# 3_viper_eagle_rep-mcu.net
KiCad netlist of a schematic drawn in Altium Designer
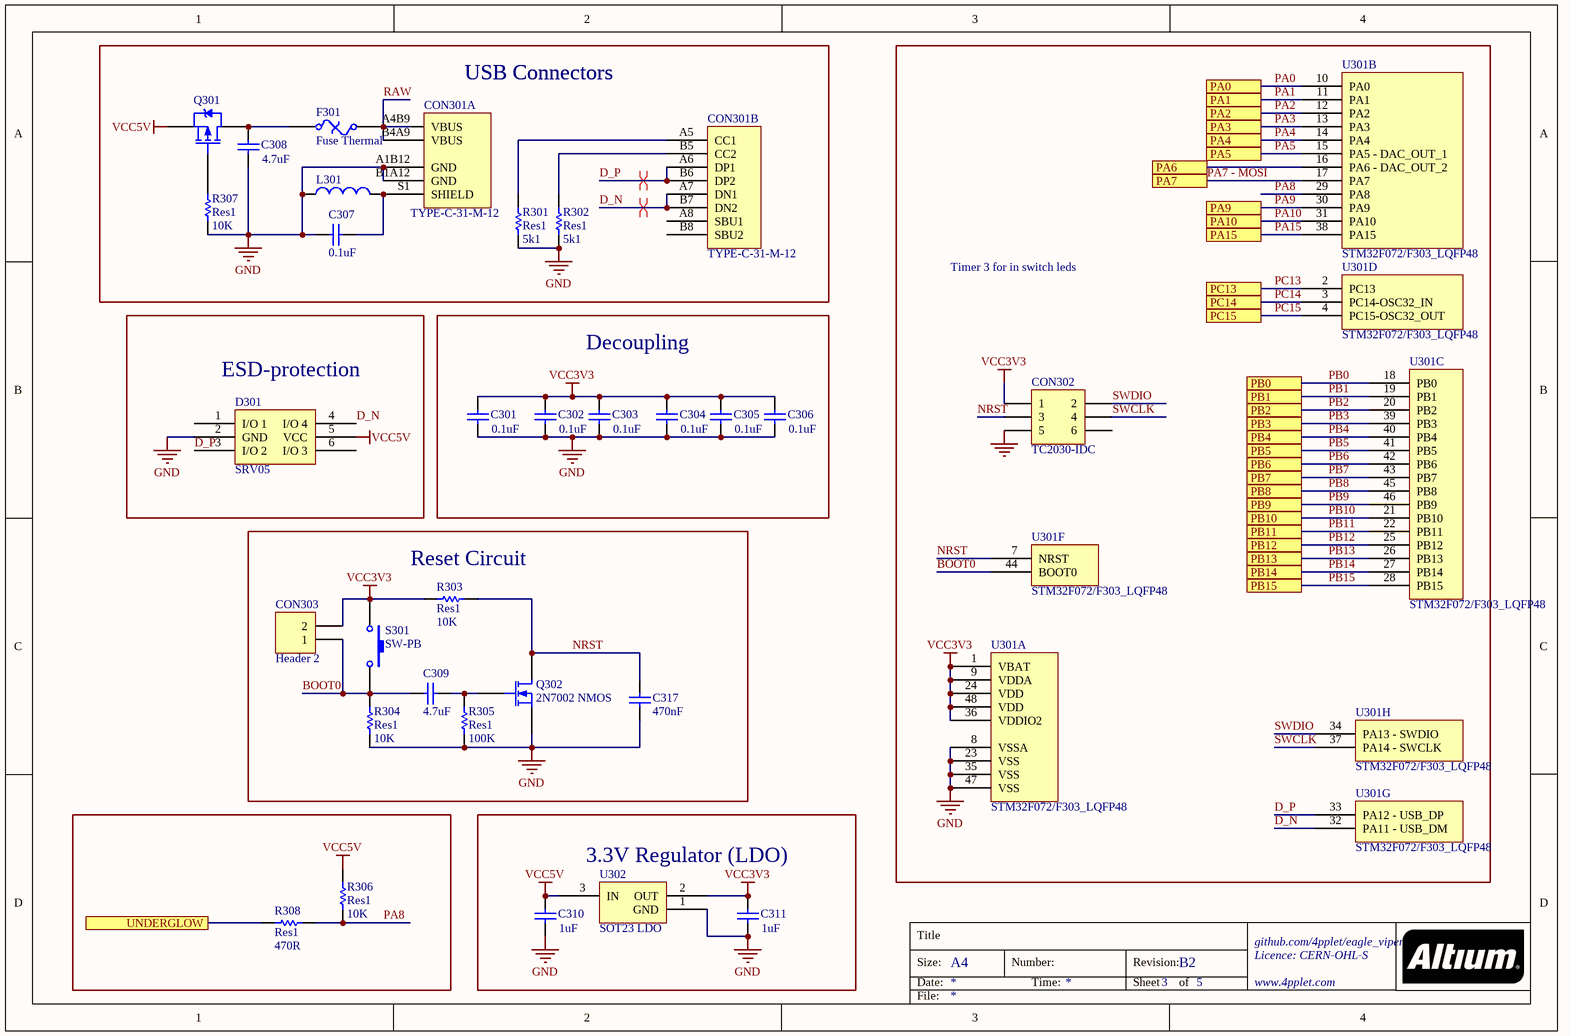
[diagram p0: 3_viper_eagle_rep-mcu.SchDoc]

(export (version "E")
  (design (tool "Eeschema 10.0.6"))
  (components
    (comp (ref "C301")
      (value "0.1uF")
      (footprint "C0603[1608]")
      (description "Capacitor")
      (fields (field (name "LCSC PART #") "C14663") (field (name "MRF.PART") "CC0603KRX7R9BB104"))
      (libsource (lib "Miscellaneous Devices") (part "Cap"))
    )
    (comp (ref "C302")
      (value "0.1uF")
      (footprint "C0603[1608]")
      (description "Capacitor")
      (fields (field (name "LCSC PART #") "C14663") (field (name "MRF.PART") "CC0603KRX7R9BB104"))
      (libsource (lib "Miscellaneous Devices") (part "Cap"))
    )
    (comp (ref "C303")
      (value "0.1uF")
      (footprint "C0603[1608]")
      (description "Capacitor")
      (fields (field (name "LCSC PART #") "C14663") (field (name "MRF.PART") "CC0603KRX7R9BB104"))
      (libsource (lib "Miscellaneous Devices") (part "Cap"))
    )
    (comp (ref "C304")
      (value "0.1uF")
      (footprint "C0603[1608]")
      (description "Capacitor")
      (fields (field (name "LCSC PART #") "C14663") (field (name "MRF.PART") "CC0603KRX7R9BB104"))
      (libsource (lib "Miscellaneous Devices") (part "Cap"))
    )
    (comp (ref "C305")
      (value "0.1uF")
      (footprint "C0603[1608]")
      (description "Capacitor")
      (fields (field (name "LCSC PART #") "C14663") (field (name "MRF.PART") "CC0603KRX7R9BB104"))
      (libsource (lib "Miscellaneous Devices") (part "Cap"))
    )
    (comp (ref "C306")
      (value "0.1uF")
      (footprint "C0603[1608]")
      (description "Capacitor")
      (fields (field (name "LCSC PART #") "C14663") (field (name "MRF.PART") "CC0603KRX7R9BB104"))
      (libsource (lib "Miscellaneous Devices") (part "Cap"))
    )
    (comp (ref "C307")
      (value "0.1uF")
      (footprint "C0603[1608]")
      (description "Capacitor")
      (fields (field (name "LCSC PART #") "C14663") (field (name "MRF.PART") "CC0603KRX7R9BB104"))
      (libsource (lib "Miscellaneous Devices") (part "Cap"))
    )
    (comp (ref "C308")
      (value "4.7uF")
      (footprint "C0603[1608]")
      (description "Capacitor")
      (fields (field (name "LCSC PART #") "C19666") (field (name "MRF.PART") "CL10A475KO8NNNC"))
      (libsource (lib "Miscellaneous Devices") (part "Cap"))
    )
    (comp (ref "C309")
      (value "4.7uF")
      (footprint "C0603[1608]")
      (description "Capacitor")
      (fields (field (name "LCSC PART #") "C19666") (field (name "MRF.PART") "CL10A475KO8NNNC"))
      (libsource (lib "Miscellaneous Devices") (part "Cap"))
    )
    (comp (ref "C310")
      (value "1uF")
      (footprint "C0603[1608]")
      (description "Capacitor")
      (fields (field (name "LCSC PART #") "C15849") (field (name "MRF.PART") "CL10A105KB8NNNC"))
      (libsource (lib "Miscellaneous Devices") (part "Cap"))
    )
    (comp (ref "C311")
      (value "1uF")
      (footprint "C0603[1608]")
      (description "Capacitor")
      (fields (field (name "LCSC PART #") "C15849") (field (name "MRF.PART") "CL10A105KB8NNNC"))
      (libsource (lib "Miscellaneous Devices") (part "Cap"))
    )
    (comp (ref "C317")
      (value "470nF")
      (footprint "C0603[1608]")
      (description "Capacitor")
      (fields (field (name "LCSC PART #") "C1623") (field (name "MRF.PART") "CL10B474KA8NNNC"))
      (libsource (lib "Miscellaneous Devices") (part "Cap"))
    )
    (comp (ref "CON301")
      (value "TYPE-C-31-M-12")
      (footprint "TYPE-C-31-M-12")
      (fields (field (name "LCSC PART #") "C165948"))
      (libsource (lib "Schlib1") (part "TYPE-C-31-M-12"))
    )
    (comp (ref "CON302")
      (value "TC2030-IDC")
      (footprint "TC2030-IDC-NL")
      (description "Header, 3-Pin, Dual row")
      (libsource (lib "Miscellaneous Connectors") (part "Header 3X2"))
    )
    (comp (ref "CON303")
      (value "Header 2")
      (footprint "HDR1X2")
      (description "Header, 2-Pin")
      (libsource (lib "Miscellaneous Connectors") (part "Header 2"))
    )
    (comp (ref "D301")
      (value "SRV05")
      (footprint "SOT-23-6")
      (fields (field (name "LCSC PART #") "C85364") (field (name "MRF.PART") "SRV05-4-P-T7"))
      (libsource (lib "Keebs") (part "SRV05"))
    )
    (comp (ref "F301")
      (value "Fuse Thermal")
      (footprint "C1206[3216]")
      (description "Thermal Fuse")
      (fields (field (name "LCSC PART #") "C135338") (field (name "MRF.PART") "ASMD1206-050"))
      (libsource (lib "Miscellaneous Devices") (part "Fuse Thermal"))
    )
    (comp (ref "L301")
      (value "Inductor")
      (footprint "L0805")
      (fields (field (name "LCSC PART #") "C1015") (field (name "MRF.PART") "GZ2012D101TF"))
      (libsource (lib "Simulation Generic Components") (part "Inductor"))
    )
    (comp (ref "Q301")
      (value "PMOS-2")
      (footprint "SOT-23-3")
      (description "P-Channel Power MOSFET")
      (fields (field (name "LCSC PART #") "C10487") (field (name "MRF.PART") "SI2301CDS-T1-GE3"))
      (libsource (lib "Miscellaneous Devices") (part "PMOS-2"))
    )
    (comp (ref "Q302")
      (value "2N7002 NMOS")
      (footprint "SOT-23-3")
      (description "N-Channel MOSFET")
      (fields (field (name "LCSC PART #") "C8545") (field (name "MRF.PART") "2N7002"))
      (libsource (lib "Miscellaneous Devices") (part "MOSFET-N"))
    )
    (comp (ref "R301")
      (value "Res1")
      (footprint "R0603[1608]")
      (description "Resistor")
      (fields
        (field (name "ALTIUM_VALUE") "5k1")
        (field (name "LCSC PART #") "C23186")
        (field (name "MRF.PART") "0603WAF5101T5E")
      )
      (libsource (lib "Miscellaneous Devices") (part "Res1"))
    )
    (comp (ref "R302")
      (value "Res1")
      (footprint "R0603[1608]")
      (description "Resistor")
      (fields
        (field (name "ALTIUM_VALUE") "5k1")
        (field (name "LCSC PART #") "C23186")
        (field (name "MRF.PART") "0603WAF5101T5E")
      )
      (libsource (lib "Miscellaneous Devices") (part "Res1"))
    )
    (comp (ref "R303")
      (value "Res1")
      (footprint "R0603[1608]")
      (description "Resistor")
      (fields
        (field (name "ALTIUM_VALUE") "10K")
        (field (name "LCSC PART #") "C25804")
        (field (name "MRF.PART") "0603WAF1002T5E")
      )
      (libsource (lib "Miscellaneous Devices") (part "Res1"))
    )
    (comp (ref "R304")
      (value "Res1")
      (footprint "R0603[1608]")
      (description "Resistor")
      (fields
        (field (name "ALTIUM_VALUE") "10K")
        (field (name "LCSC PART #") "C25804")
        (field (name "MRF.PART") "0603WAF1002T5E")
      )
      (libsource (lib "Miscellaneous Devices") (part "Res1"))
    )
    (comp (ref "R305")
      (value "Res1")
      (footprint "R0603[1608]")
      (description "Resistor")
      (fields
        (field (name "ALTIUM_VALUE") "100K")
        (field (name "LCSC PART #") "C25803")
        (field (name "MRF.PART") "0603WAF1003T5E")
      )
      (libsource (lib "Miscellaneous Devices") (part "Res1"))
    )
    (comp (ref "R306")
      (value "Res1")
      (footprint "R0603[1608]")
      (description "Resistor")
      (fields
        (field (name "ALTIUM_VALUE") "10K")
        (field (name "LCSC PART #") "C25804")
        (field (name "MRF.PART") "0603WAF1002T5E")
      )
      (libsource (lib "Miscellaneous Devices") (part "Res1"))
    )
    (comp (ref "R307")
      (value "Res1")
      (footprint "R0603[1608]")
      (description "Resistor")
      (fields
        (field (name "ALTIUM_VALUE") "10K")
        (field (name "LCSC PART #") "C25804")
        (field (name "MRF.PART") "0603WAF1002T5E")
      )
      (libsource (lib "Miscellaneous Devices") (part "Res1"))
    )
    (comp (ref "R308")
      (value "Res1")
      (footprint "R0603[1608]")
      (description "Resistor")
      (fields
        (field (name "ALTIUM_VALUE") "470R")
        (field (name "LCSC PART #") "C23179")
        (field (name "MRF.PART") "0603WAF4700T5E")
      )
      (libsource (lib "Miscellaneous Devices") (part "Res1"))
    )
    (comp (ref "S301")
      (value "SW-PB")
      (footprint "XKB Switch")
      (description "Switch")
      (fields (field (name "MRF.PART") "TS-1187A-C-D-B") (field (name "LCSC PART #") "C318888"))
      (libsource (lib "Miscellaneous Devices") (part "SW-PB"))
    )
    (comp (ref "U301")
      (value "STM32F072/F303_LQFP48")
      (footprint "STM32 - COMBO 7X7MM")
      (fields (field (name "LCSC PART #") "C915660") (field (name "MRF.PART") "APM32F072CBT6"))
      (libsource (lib "Keebs") (part "STM32F072/F303_LQFP48"))
    )
    (comp (ref "U302")
      (value "SOT23 LDO")
      (footprint "SOT-23-3")
      (fields (field (name "LCSC PART #") "C5446") (field (name "MRF.PART") "XC6206P332MR"))
      (libsource (lib "Keebs") (part "SOT23 LDO"))
    )
  )
  (nets
    (net (code "1") (name "/BOOT0") (class "Default")
      (node (ref "C309") (pin "2") (pinfunction "2_2") (pintype "passive"))
      (node (ref "CON303") (pin "1") (pinfunction "1_1") (pintype "passive"))
      (node (ref "R304") (pin "1") (pinfunction "1_1") (pintype "passive"))
      (node (ref "S301") (pin "2") (pinfunction "2_2") (pintype "passive"))
      (node (ref "U301") (pin "44") (pinfunction "BOOT0_44") (pintype "passive"))
    )
    (net (code "2") (name "/D_N") (class "Default")
      (node (ref "CON301") (pin "A7") (pinfunction "DN1_A7") (pintype "passive"))
      (node (ref "CON301") (pin "B7") (pinfunction "DN2_B7") (pintype "passive"))
      (node (ref "D301") (pin "4") (pinfunction "I/O_4_4") (pintype "passive"))
      (node (ref "U301") (pin "32") (pinfunction "PA11_-_USB_DM_32") (pintype "passive"))
    )
    (net (code "3") (name "/D_P") (class "Default")
      (node (ref "CON301") (pin "A6") (pinfunction "DP1_A6") (pintype "passive"))
      (node (ref "CON301") (pin "B6") (pinfunction "DP2_B6") (pintype "passive"))
      (node (ref "D301") (pin "3") (pinfunction "I/O_2_3") (pintype "passive"))
      (node (ref "U301") (pin "33") (pinfunction "PA12_-_USB_DP_33") (pintype "passive"))
    )
    (net (code "4") (name "/NRST") (class "Default")
      (node (ref "C317") (pin "1") (pinfunction "1_1") (pintype "passive"))
      (node (ref "CON302") (pin "3") (pinfunction "3_3") (pintype "passive"))
      (node (ref "Q302") (pin "3") (pinfunction "D_3") (pintype "passive"))
      (node (ref "R303") (pin "2") (pinfunction "2_2") (pintype "passive"))
      (node (ref "U301") (pin "7") (pinfunction "NRST_7") (pintype "passive"))
    )
    (net (code "5") (name "/PA0") (class "Default")
      (node (ref "U301") (pin "10") (pinfunction "PA0_10") (pintype "passive"))
    )
    (net (code "6") (name "/PA1") (class "Default")
      (node (ref "U301") (pin "11") (pinfunction "PA1_11") (pintype "passive"))
    )
    (net (code "7") (name "/PA2") (class "Default")
      (node (ref "U301") (pin "12") (pinfunction "PA2_12") (pintype "passive"))
    )
    (net (code "8") (name "/PA3") (class "Default")
      (node (ref "U301") (pin "13") (pinfunction "PA3_13") (pintype "passive"))
    )
    (net (code "9") (name "/PA4") (class "Default")
      (node (ref "U301") (pin "14") (pinfunction "PA4_14") (pintype "passive"))
    )
    (net (code "10") (name "/PA5") (class "Default")
      (node (ref "U301") (pin "15") (pinfunction "PA5_-_DAC_OUT_1_15") (pintype "passive"))
    )
    (net (code "11") (name "/PA6") (class "Default")
      (node (ref "U301") (pin "16") (pinfunction "PA6_-_DAC_OUT_2_16") (pintype "passive"))
    )
    (net (code "12") (name "/PA7 - MOSI") (class "Default")
      (node (ref "U301") (pin "17") (pinfunction "PA7_17") (pintype "passive"))
    )
    (net (code "13") (name "/PA8") (class "Default")
      (node (ref "R306") (pin "2") (pinfunction "2_2") (pintype "passive"))
      (node (ref "R308") (pin "1") (pinfunction "1_1") (pintype "passive"))
      (node (ref "U301") (pin "29") (pinfunction "PA8_29") (pintype "passive"))
    )
    (net (code "14") (name "/PA9") (class "Default")
      (node (ref "U301") (pin "30") (pinfunction "PA9_30") (pintype "passive"))
    )
    (net (code "15") (name "/PA10") (class "Default")
      (node (ref "U301") (pin "31") (pinfunction "PA10_31") (pintype "passive"))
    )
    (net (code "16") (name "/PA15") (class "Default")
      (node (ref "U301") (pin "38") (pinfunction "PA15_38") (pintype "passive"))
    )
    (net (code "17") (name "/PB0") (class "Default")
      (node (ref "U301") (pin "18") (pinfunction "PB0_18") (pintype "passive"))
    )
    (net (code "18") (name "/PB1") (class "Default")
      (node (ref "U301") (pin "19") (pinfunction "PB1_19") (pintype "passive"))
    )
    (net (code "19") (name "/PB2") (class "Default")
      (node (ref "U301") (pin "20") (pinfunction "PB2_20") (pintype "passive"))
    )
    (net (code "20") (name "/PB3") (class "Default")
      (node (ref "U301") (pin "39") (pinfunction "PB3_39") (pintype "passive"))
    )
    (net (code "21") (name "/PB4") (class "Default")
      (node (ref "U301") (pin "40") (pinfunction "PB4_40") (pintype "passive"))
    )
    (net (code "22") (name "/PB5") (class "Default")
      (node (ref "U301") (pin "41") (pinfunction "PB5_41") (pintype "passive"))
    )
    (net (code "23") (name "/PB6") (class "Default")
      (node (ref "U301") (pin "42") (pinfunction "PB6_42") (pintype "passive"))
    )
    (net (code "24") (name "/PB7") (class "Default")
      (node (ref "U301") (pin "43") (pinfunction "PB7_43") (pintype "passive"))
    )
    (net (code "25") (name "/PB8") (class "Default")
      (node (ref "U301") (pin "45") (pinfunction "PB8_45") (pintype "passive"))
    )
    (net (code "26") (name "/PB9") (class "Default")
      (node (ref "U301") (pin "46") (pinfunction "PB9_46") (pintype "passive"))
    )
    (net (code "27") (name "/PB10") (class "Default")
      (node (ref "U301") (pin "21") (pinfunction "PB10_21") (pintype "passive"))
    )
    (net (code "28") (name "/PB11") (class "Default")
      (node (ref "U301") (pin "22") (pinfunction "PB11_22") (pintype "passive"))
    )
    (net (code "29") (name "/PB12") (class "Default")
      (node (ref "U301") (pin "25") (pinfunction "PB12_25") (pintype "passive"))
    )
    (net (code "30") (name "/PB13") (class "Default")
      (node (ref "U301") (pin "26") (pinfunction "PB13_26") (pintype "passive"))
    )
    (net (code "31") (name "/PB14") (class "Default")
      (node (ref "U301") (pin "27") (pinfunction "PB14_27") (pintype "passive"))
    )
    (net (code "32") (name "/PB15") (class "Default")
      (node (ref "U301") (pin "28") (pinfunction "PB15_28") (pintype "passive"))
    )
    (net (code "33") (name "/PC13") (class "Default")
      (node (ref "U301") (pin "2") (pinfunction "PC13_2") (pintype "passive"))
    )
    (net (code "34") (name "/PC14") (class "Default")
      (node (ref "U301") (pin "3") (pinfunction "PC14-OSC32_IN_3") (pintype "passive"))
    )
    (net (code "35") (name "/PC15") (class "Default")
      (node (ref "U301") (pin "4") (pinfunction "PC15-OSC32_OUT_4") (pintype "passive"))
    )
    (net (code "36") (name "/RAW") (class "Default")
      (node (ref "CON301") (pin "A4B9") (pinfunction "VBUS_A4B9") (pintype "passive"))
      (node (ref "CON301") (pin "B4A9") (pinfunction "VBUS_B4A9") (pintype "passive"))
      (node (ref "F301") (pin "2") (pinfunction "2_2") (pintype "passive"))
    )
    (net (code "37") (name "/SWCLK") (class "Default")
      (node (ref "CON302") (pin "4") (pinfunction "4_4") (pintype "passive"))
      (node (ref "U301") (pin "37") (pinfunction "PA14_-_SWCLK_37") (pintype "passive"))
    )
    (net (code "38") (name "/SWDIO") (class "Default")
      (node (ref "CON302") (pin "2") (pinfunction "2_2") (pintype "passive"))
      (node (ref "U301") (pin "34") (pinfunction "PA13_-_SWDIO_34") (pintype "passive"))
    )
    (net (code "39") (name "/UNDERGLOW") (class "Default")
      (node (ref "R308") (pin "2") (pinfunction "2_2") (pintype "passive"))
    )
    (net (code "40") (name "GND") (class "Default")
      (node (ref "C301") (pin "1") (pinfunction "1_1") (pintype "passive"))
      (node (ref "C302") (pin "1") (pinfunction "1_1") (pintype "passive"))
      (node (ref "C303") (pin "1") (pinfunction "1_1") (pintype "passive"))
      (node (ref "C304") (pin "1") (pinfunction "1_1") (pintype "passive"))
      (node (ref "C305") (pin "1") (pinfunction "1_1") (pintype "passive"))
      (node (ref "C306") (pin "1") (pinfunction "1_1") (pintype "passive"))
      (node (ref "C307") (pin "1") (pinfunction "1_1") (pintype "passive"))
      (node (ref "C308") (pin "1") (pinfunction "1_1") (pintype "passive"))
      (node (ref "C310") (pin "1") (pinfunction "1_1") (pintype "passive"))
      (node (ref "C311") (pin "1") (pinfunction "1_1") (pintype "passive"))
      (node (ref "C317") (pin "2") (pinfunction "2_2") (pintype "passive"))
      (node (ref "CON301") (pin "A1B12") (pinfunction "GND_A1B12") (pintype "passive"))
      (node (ref "CON301") (pin "B1A12") (pinfunction "GND_B1A12") (pintype "passive"))
      (node (ref "CON302") (pin "5") (pinfunction "5_5") (pintype "passive"))
      (node (ref "D301") (pin "2") (pinfunction "GND_2") (pintype "passive"))
      (node (ref "L301") (pin "1") (pinfunction "1_1") (pintype "passive"))
      (node (ref "Q302") (pin "2") (pinfunction "S_2") (pintype "passive"))
      (node (ref "R301") (pin "2") (pinfunction "2_2") (pintype "passive"))
      (node (ref "R302") (pin "2") (pinfunction "2_2") (pintype "passive"))
      (node (ref "R304") (pin "2") (pinfunction "2_2") (pintype "passive"))
      (node (ref "R305") (pin "2") (pinfunction "2_2") (pintype "passive"))
      (node (ref "R307") (pin "2") (pinfunction "2_2") (pintype "passive"))
      (node (ref "U301") (pin "23") (pinfunction "VSS_23") (pintype "passive"))
      (node (ref "U301") (pin "35") (pinfunction "VSS_35") (pintype "passive"))
      (node (ref "U301") (pin "47") (pinfunction "VSS_47") (pintype "passive"))
      (node (ref "U301") (pin "8") (pinfunction "VSSA_8") (pintype "passive"))
      (node (ref "U302") (pin "1") (pinfunction "GND_1") (pintype "passive"))
    )
    (net (code "41") (name "Net-(CON301A-SHIELD)") (class "Default")
      (node (ref "C307") (pin "2") (pinfunction "2_2") (pintype "passive"))
      (node (ref "CON301") (pin "S1") (pinfunction "SHIELD_S1") (pintype "passive"))
      (node (ref "L301") (pin "2") (pinfunction "2_2") (pintype "passive"))
    )
    (net (code "42") (name "Net-(CON301B-CC1)") (class "Default")
      (node (ref "CON301") (pin "A5") (pinfunction "CC1_A5") (pintype "passive"))
      (node (ref "R301") (pin "1") (pinfunction "1_1") (pintype "passive"))
    )
    (net (code "43") (name "Net-(CON301B-CC2)") (class "Default")
      (node (ref "CON301") (pin "B5") (pinfunction "CC2_B5") (pintype "passive"))
      (node (ref "R302") (pin "1") (pinfunction "1_1") (pintype "passive"))
    )
    (net (code "44") (name "Net-(Q301-D)") (class "Default")
      (node (ref "C308") (pin "2") (pinfunction "2_2") (pintype "passive"))
      (node (ref "F301") (pin "1") (pinfunction "1_1") (pintype "passive"))
      (node (ref "Q301") (pin "3") (pinfunction "D_3") (pintype "passive"))
    )
    (net (code "45") (name "Net-(Q301-G)") (class "Default")
      (node (ref "Q301") (pin "1") (pinfunction "G_1") (pintype "passive"))
      (node (ref "R307") (pin "1") (pinfunction "1_1") (pintype "passive"))
    )
    (net (code "46") (name "Net-(Q302-G)") (class "Default")
      (node (ref "C309") (pin "1") (pinfunction "1_1") (pintype "passive"))
      (node (ref "Q302") (pin "1") (pinfunction "G_1") (pintype "passive"))
      (node (ref "R305") (pin "1") (pinfunction "1_1") (pintype "passive"))
    )
    (net (code "47") (name "VCC3V3") (class "Default")
      (node (ref "C301") (pin "2") (pinfunction "2_2") (pintype "passive"))
      (node (ref "C302") (pin "2") (pinfunction "2_2") (pintype "passive"))
      (node (ref "C303") (pin "2") (pinfunction "2_2") (pintype "passive"))
      (node (ref "C304") (pin "2") (pinfunction "2_2") (pintype "passive"))
      (node (ref "C305") (pin "2") (pinfunction "2_2") (pintype "passive"))
      (node (ref "C306") (pin "2") (pinfunction "2_2") (pintype "passive"))
      (node (ref "C311") (pin "2") (pinfunction "2_2") (pintype "passive"))
      (node (ref "CON302") (pin "1") (pinfunction "1_1") (pintype "passive"))
      (node (ref "CON303") (pin "2") (pinfunction "2_2") (pintype "passive"))
      (node (ref "R303") (pin "1") (pinfunction "1_1") (pintype "passive"))
      (node (ref "S301") (pin "1") (pinfunction "1_1") (pintype "passive"))
      (node (ref "U301") (pin "1") (pinfunction "VBAT_1") (pintype "passive"))
      (node (ref "U301") (pin "24") (pinfunction "VDD_24") (pintype "passive"))
      (node (ref "U301") (pin "36") (pinfunction "VDDIO2_36") (pintype "passive"))
      (node (ref "U301") (pin "48") (pinfunction "VDD_48") (pintype "passive"))
      (node (ref "U301") (pin "9") (pinfunction "VDDA_9") (pintype "passive"))
      (node (ref "U302") (pin "2") (pinfunction "OUT_2") (pintype "passive"))
    )
    (net (code "48") (name "VCC5V") (class "Default")
      (node (ref "C310") (pin "2") (pinfunction "2_2") (pintype "passive"))
      (node (ref "D301") (pin "5") (pinfunction "VCC_5") (pintype "passive"))
      (node (ref "Q301") (pin "2") (pinfunction "S_2") (pintype "passive"))
      (node (ref "R306") (pin "1") (pinfunction "1_1") (pintype "passive"))
      (node (ref "U302") (pin "3") (pinfunction "IN_3") (pintype "passive"))
    )
    (net (code "49") (name "unconnected-(CON301B-SBU1-PadA8)") (class "Default")
      (node (ref "CON301") (pin "A8") (pinfunction "SBU1_A8") (pintype "passive"))
    )
    (net (code "50") (name "unconnected-(CON301B-SBU2-PadB8)") (class "Default")
      (node (ref "CON301") (pin "B8") (pinfunction "SBU2_B8") (pintype "passive"))
    )
    (net (code "51") (name "unconnected-(CON302-Pad6)") (class "Default")
      (node (ref "CON302") (pin "6") (pinfunction "6_6") (pintype "passive"))
    )
    (net (code "52") (name "unconnected-(D301-I{slash}O_1-Pad1)") (class "Default")
      (node (ref "D301") (pin "1") (pinfunction "I/O_1_1") (pintype "passive"))
    )
    (net (code "53") (name "unconnected-(D301-I{slash}O_3-Pad6)") (class "Default")
      (node (ref "D301") (pin "6") (pinfunction "I/O_3_6") (pintype "passive"))
    )
  )
)
